# Ports.net
KiCad netlist of a schematic drawn in Altium Designer
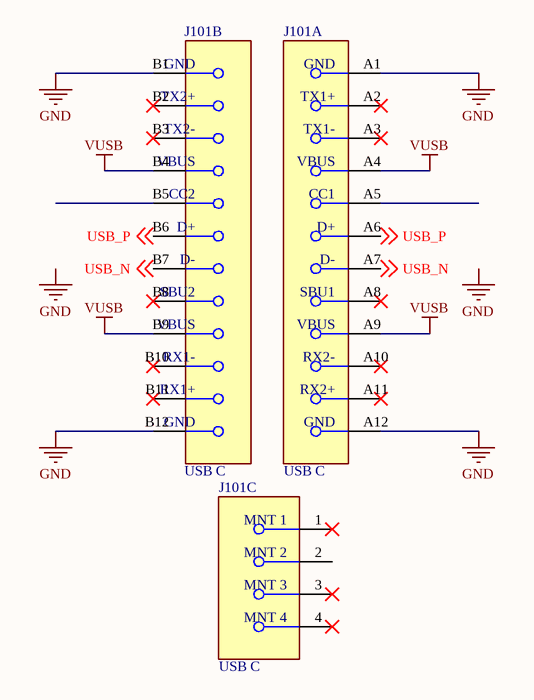
[diagram p0: Ports.SchDoc]

(export (version "E")
  (design (tool "Eeschema 10.0.6"))
  (components
    (comp (ref "J101")
      (value "USB C")
      (footprint "FP-1054500101-MFG")
      (description "CONN RCP USB3.1 TYPEC 24P SMD RA")
      (fields
        (field (name "MANUFACTURER") "Molex")
        (field (name "OCTOPART") "https://octopart.com/105450-0101-molex-68082325")
      )
      (libsource (lib "Main") (part "1054500101"))
    )
  )
  (nets
    (net (code "1") (name "GND") (class "Default")
      (node (ref "J101") (pin "A1") (pinfunction "GND_A1") (pintype "passive"))
      (node (ref "J101") (pin "A12") (pinfunction "GND_A12") (pintype "passive"))
      (node (ref "J101") (pin "B1") (pinfunction "GND_B1") (pintype "passive"))
      (node (ref "J101") (pin "B12") (pinfunction "GND_B12") (pintype "passive"))
    )
    (net (code "2") (name "USB_N") (class "Default")
      (node (ref "J101") (pin "A7") (pinfunction "D-_A7") (pintype "passive"))
      (node (ref "J101") (pin "B7") (pinfunction "D-_B7") (pintype "passive"))
    )
    (net (code "3") (name "USB_P") (class "Default")
      (node (ref "J101") (pin "A6") (pinfunction "D+_A6") (pintype "passive"))
      (node (ref "J101") (pin "B6") (pinfunction "D+_B6") (pintype "passive"))
    )
    (net (code "4") (name "VUSB") (class "Default")
      (node (ref "J101") (pin "A4") (pinfunction "VBUS_A4") (pintype "passive"))
      (node (ref "J101") (pin "A9") (pinfunction "VBUS_A9") (pintype "passive"))
      (node (ref "J101") (pin "B4") (pinfunction "VBUS_B4") (pintype "passive"))
      (node (ref "J101") (pin "B9") (pinfunction "VBUS_B9") (pintype "passive"))
    )
    (net (code "5") (name "unconnected-(J101A-CC1-PadA5)") (class "Default")
      (node (ref "J101") (pin "A5") (pinfunction "CC1_A5") (pintype "passive"))
    )
    (net (code "6") (name "unconnected-(J101A-RX2+-PadA11)") (class "Default")
      (node (ref "J101") (pin "A11") (pinfunction "RX2+_A11") (pintype "passive+no_connect"))
    )
    (net (code "7") (name "unconnected-(J101A-RX2--PadA10)") (class "Default")
      (node (ref "J101") (pin "A10") (pinfunction "RX2-_A10") (pintype "passive+no_connect"))
    )
    (net (code "8") (name "unconnected-(J101A-SBU1-PadA8)") (class "Default")
      (node (ref "J101") (pin "A8") (pinfunction "SBU1_A8") (pintype "passive+no_connect"))
    )
    (net (code "9") (name "unconnected-(J101A-TX1+-PadA2)") (class "Default")
      (node (ref "J101") (pin "A2") (pinfunction "TX1+_A2") (pintype "passive+no_connect"))
    )
    (net (code "10") (name "unconnected-(J101A-TX1--PadA3)") (class "Default")
      (node (ref "J101") (pin "A3") (pinfunction "TX1-_A3") (pintype "passive+no_connect"))
    )
    (net (code "11") (name "unconnected-(J101B-CC2-PadB5)") (class "Default")
      (node (ref "J101") (pin "B5") (pinfunction "CC2_B5") (pintype "passive"))
    )
    (net (code "12") (name "unconnected-(J101B-RX1+-PadB11)") (class "Default")
      (node (ref "J101") (pin "B11") (pinfunction "RX1+_B11") (pintype "passive+no_connect"))
    )
    (net (code "13") (name "unconnected-(J101B-RX1--PadB10)") (class "Default")
      (node (ref "J101") (pin "B10") (pinfunction "RX1-_B10") (pintype "passive+no_connect"))
    )
    (net (code "14") (name "unconnected-(J101B-SBU2-PadB8)") (class "Default")
      (node (ref "J101") (pin "B8") (pinfunction "SBU2_B8") (pintype "passive+no_connect"))
    )
    (net (code "15") (name "unconnected-(J101B-TX2+-PadB2)") (class "Default")
      (node (ref "J101") (pin "B2") (pinfunction "TX2+_B2") (pintype "passive+no_connect"))
    )
    (net (code "16") (name "unconnected-(J101B-TX2--PadB3)") (class "Default")
      (node (ref "J101") (pin "B3") (pinfunction "TX2-_B3") (pintype "passive+no_connect"))
    )
    (net (code "17") (name "unconnected-(J101C-MNT_1-Pad1)") (class "Default")
      (node (ref "J101") (pin "1") (pinfunction "MNT_1_1") (pintype "passive+no_connect"))
    )
    (net (code "18") (name "unconnected-(J101C-MNT_2-Pad2)") (class "Default")
      (node (ref "J101") (pin "2") (pinfunction "MNT_2_2") (pintype "passive"))
    )
    (net (code "19") (name "unconnected-(J101C-MNT_3-Pad3)") (class "Default")
      (node (ref "J101") (pin "3") (pinfunction "MNT_3_3") (pintype "passive+no_connect"))
    )
    (net (code "20") (name "unconnected-(J101C-MNT_4-Pad4)") (class "Default")
      (node (ref "J101") (pin "4") (pinfunction "MNT_4_4") (pintype "passive+no_connect"))
    )
  )
)
